# atommc-extender.net
KiCad netlist of a schematic drawn in EAGLE
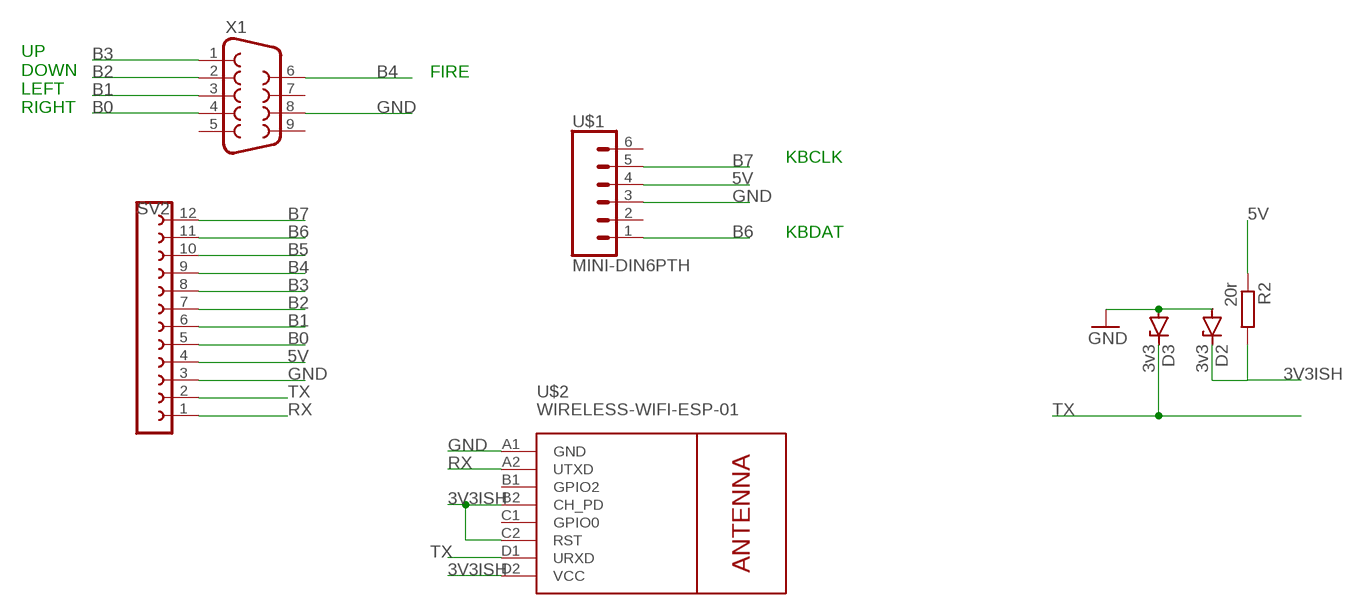
[diagram p0: schematic, sheet 1]

(export (version "E")
  (design (tool "Eeschema 10.0.6"))
  (components
    (comp (ref "D2")
      (value "3v3")
      (footprint "eagle-import:DO34Z7")
      (libsource (lib "eagle-import") (part "ZENER-DIODEDO34-7"))
    )
    (comp (ref "D3")
      (value "3v3")
      (footprint "eagle-import:DO34Z7")
      (libsource (lib "eagle-import") (part "ZENER-DIODEDO34-7"))
    )
    (comp (ref "R2")
      (value "20r")
      (footprint "eagle-import:0207_10")
      (libsource (lib "eagle-import") (part "R-EU_0207/10"))
    )
    (comp (ref "SV2")
      (value "FE12-1")
      (footprint "eagle-import:FE12")
      (libsource (lib "eagle-import") (part "FE12-1"))
    )
    (comp (ref "U$1")
      (value "MINI-DIN6PTH")
      (footprint "eagle-import:MINI-DIN6")
      (libsource (lib "eagle-import") (part "MINI-DIN6PTH"))
    )
    (comp (ref "U$2")
      (value "WIRELESS-WIFI-ESP-01")
      (footprint "eagle-import:WIRELESS-WIFI-ESP-01")
      (libsource (lib "eagle-import") (part "WIRELESS-WIFI-ESP-01"))
    )
    (comp (ref "X1")
      (value "F09V")
      (footprint "eagle-import:F09V")
      (libsource (lib "eagle-import") (part "F09V"))
    )
  )
  (nets
    (net (code "1") (name "/3V3ISH") (class "Default")
      (node (ref "D2") (pin "C") (pinfunction "C_C") (pintype "passive"))
      (node (ref "R2") (pin "2") (pinfunction "2_2") (pintype "passive"))
      (node (ref "U$2") (pin "B2") (pinfunction "CH_PD_B2") (pintype "bidirectional"))
      (node (ref "U$2") (pin "C2") (pinfunction "RST_C2") (pintype "bidirectional"))
      (node (ref "U$2") (pin "D2") (pinfunction "VCC_D2") (pintype "power_in"))
    )
    (net (code "2") (name "/5V") (class "Default")
      (node (ref "R2") (pin "1") (pinfunction "1_1") (pintype "passive"))
      (node (ref "SV2") (pin "4") (pinfunction "4_4") (pintype "passive"))
      (node (ref "U$1") (pin "4") (pinfunction "4_4") (pintype "passive"))
    )
    (net (code "3") (name "/B0") (class "Default")
      (node (ref "SV2") (pin "5") (pinfunction "5_5") (pintype "passive"))
      (node (ref "X1") (pin "4") (pinfunction "4_4") (pintype "passive"))
    )
    (net (code "4") (name "/B1") (class "Default")
      (node (ref "SV2") (pin "6") (pinfunction "6_6") (pintype "passive"))
      (node (ref "X1") (pin "3") (pinfunction "3_3") (pintype "passive"))
    )
    (net (code "5") (name "/B2") (class "Default")
      (node (ref "SV2") (pin "7") (pinfunction "7_7") (pintype "passive"))
      (node (ref "X1") (pin "2") (pinfunction "2_2") (pintype "passive"))
    )
    (net (code "6") (name "/B3") (class "Default")
      (node (ref "SV2") (pin "8") (pinfunction "8_8") (pintype "passive"))
      (node (ref "X1") (pin "1") (pinfunction "1_1") (pintype "passive"))
    )
    (net (code "7") (name "/B4") (class "Default")
      (node (ref "SV2") (pin "9") (pinfunction "9_9") (pintype "passive"))
      (node (ref "X1") (pin "6") (pinfunction "6_6") (pintype "passive"))
    )
    (net (code "8") (name "/B5") (class "Default")
      (node (ref "SV2") (pin "10") (pinfunction "10_10") (pintype "passive"))
    )
    (net (code "9") (name "/B6") (class "Default")
      (node (ref "SV2") (pin "11") (pinfunction "11_11") (pintype "passive"))
      (node (ref "U$1") (pin "1") (pinfunction "1_1") (pintype "passive"))
    )
    (net (code "10") (name "/B7") (class "Default")
      (node (ref "SV2") (pin "12") (pinfunction "12_12") (pintype "passive"))
      (node (ref "U$1") (pin "5") (pinfunction "5_5") (pintype "passive"))
    )
    (net (code "11") (name "/RX") (class "Default")
      (node (ref "SV2") (pin "1") (pinfunction "1_1") (pintype "passive"))
      (node (ref "U$2") (pin "A2") (pinfunction "UTXD_A2") (pintype "bidirectional"))
    )
    (net (code "12") (name "/TX") (class "Default")
      (node (ref "D3") (pin "C") (pinfunction "C_C") (pintype "passive"))
      (node (ref "SV2") (pin "2") (pinfunction "2_2") (pintype "passive"))
      (node (ref "U$2") (pin "D1") (pinfunction "URXD_D1") (pintype "bidirectional"))
    )
    (net (code "13") (name "GND") (class "Default")
      (node (ref "D2") (pin "A") (pinfunction "A_A") (pintype "passive"))
      (node (ref "D3") (pin "A") (pinfunction "A_A") (pintype "passive"))
      (node (ref "SV2") (pin "3") (pinfunction "3_3") (pintype "passive"))
      (node (ref "U$1") (pin "3") (pinfunction "3_3") (pintype "passive"))
      (node (ref "U$2") (pin "A1") (pinfunction "GND_A1") (pintype "power_in"))
      (node (ref "X1") (pin "8") (pinfunction "8_8") (pintype "passive"))
    )
    (net (code "14") (name "unconnected-(U$1-Pad2)") (class "Default")
      (node (ref "U$1") (pin "2") (pinfunction "2_2") (pintype "passive"))
    )
    (net (code "15") (name "unconnected-(U$1-Pad6)") (class "Default")
      (node (ref "U$1") (pin "6") (pinfunction "6_6") (pintype "passive"))
    )
    (net (code "16") (name "unconnected-(U$2-GPIO0-PadC1)") (class "Default")
      (node (ref "U$2") (pin "C1") (pinfunction "GPIO0_C1") (pintype "bidirectional"))
    )
    (net (code "17") (name "unconnected-(U$2-GPIO2-PadB1)") (class "Default")
      (node (ref "U$2") (pin "B1") (pinfunction "GPIO2_B1") (pintype "bidirectional"))
    )
    (net (code "18") (name "unconnected-(X1-Pad5)") (class "Default")
      (node (ref "X1") (pin "5") (pinfunction "5_5") (pintype "passive"))
    )
    (net (code "19") (name "unconnected-(X1-Pad7)") (class "Default")
      (node (ref "X1") (pin "7") (pinfunction "7_7") (pintype "passive"))
    )
    (net (code "20") (name "unconnected-(X1-Pad9)") (class "Default")
      (node (ref "X1") (pin "9") (pinfunction "9_9") (pintype "passive"))
    )
  )
)
